# Qwiic_GPIO.net
KiCad netlist of a schematic drawn in EAGLE
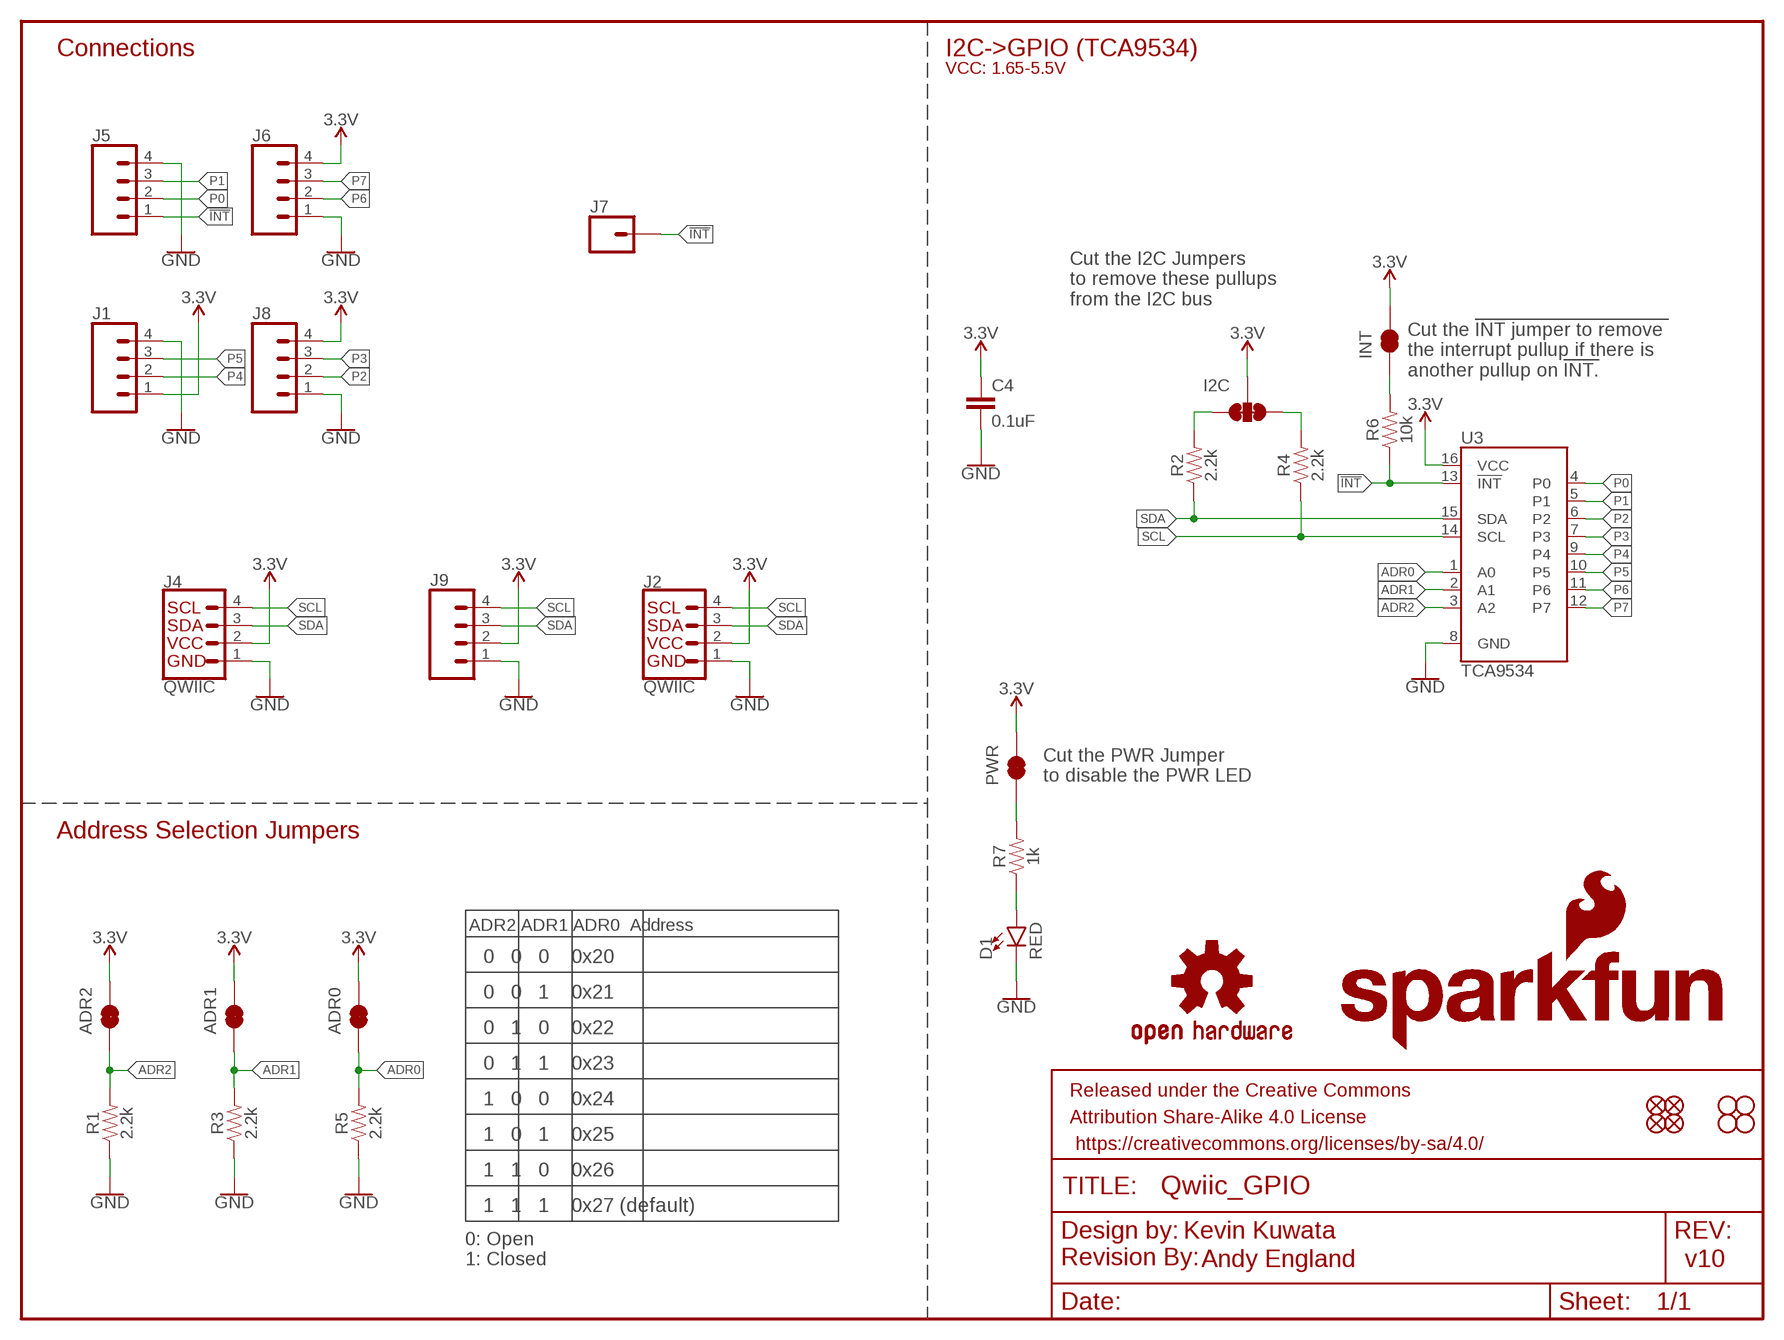
[diagram p0: schematic, sheet 1]

(export (version "E")
  (design (tool "Eeschema 10.0.6"))
  (components
    (comp (ref "ADR0")
      (value "JUMPER-SMT_2_NC_TRACE_SILK")
      (footprint "eagle-import:SMT-JUMPER_2_NC_TRACE_SILK")
      (libsource (lib "eagle-import") (part "JUMPER-SMT_2_NC_TRACE_SILK"))
    )
    (comp (ref "ADR1")
      (value "JUMPER-SMT_2_NC_TRACE_SILK")
      (footprint "eagle-import:SMT-JUMPER_2_NC_TRACE_SILK")
      (libsource (lib "eagle-import") (part "JUMPER-SMT_2_NC_TRACE_SILK"))
    )
    (comp (ref "ADR2")
      (value "JUMPER-SMT_2_NC_TRACE_SILK")
      (footprint "eagle-import:SMT-JUMPER_2_NC_TRACE_SILK")
      (libsource (lib "eagle-import") (part "JUMPER-SMT_2_NC_TRACE_SILK"))
    )
    (comp (ref "C4")
      (value "0.1uF")
      (footprint "eagle-import:0603")
      (libsource (lib "eagle-import") (part "0.1UF-0603-25V-(+80/-20%)"))
    )
    (comp (ref "D1")
      (value "RED")
      (footprint "eagle-import:LED-0603")
      (libsource (lib "eagle-import") (part "LED-RED0603"))
    )
    (comp (ref "FD1")
      (value "FIDUCIAL1X2")
      (footprint "eagle-import:FIDUCIAL-1X2")
      (libsource (lib "eagle-import") (part "SparkFun-Aesthetics_FIDUCIAL1X2"))
    )
    (comp (ref "FD2")
      (value "FIDUCIAL1X2")
      (footprint "eagle-import:FIDUCIAL-1X2")
      (libsource (lib "eagle-import") (part "SparkFun-Aesthetics_FIDUCIAL1X2"))
    )
    (comp (ref "FRAME1")
      (value "FRAME-LETTER")
      (footprint "eagle-import:CREATIVE_COMMONS")
      (libsource (lib "eagle-import") (part "FRAME-LETTER"))
    )
    (comp (ref "H1")
      (value "STAND-OFF")
      (footprint "eagle-import:STAND-OFF")
      (libsource (lib "eagle-import") (part "SparkFun-Hardware_STAND-OFF"))
    )
    (comp (ref "H2")
      (value "STAND-OFF")
      (footprint "eagle-import:STAND-OFF")
      (libsource (lib "eagle-import") (part "SparkFun-Hardware_STAND-OFF"))
    )
    (comp (ref "I2C")
      (value "JUMPER-SMT_3_2-NC_TRACE_SILK")
      (footprint "eagle-import:SMT-JUMPER_3_2-NC_TRACE_SILK")
      (libsource (lib "eagle-import") (part "JUMPER-SMT_3_2-NC_TRACE_SILK"))
    )
    (comp (ref "INT")
      (value "JUMPER-SMT_2_NC_TRACE_SILK")
      (footprint "eagle-import:SMT-JUMPER_2_NC_TRACE_SILK")
      (libsource (lib "eagle-import") (part "JUMPER-SMT_2_NC_TRACE_SILK"))
    )
    (comp (ref "J1")
      (value "CONN_04LATCH")
      (footprint "eagle-import:LATCHTERMINAL-5MM-4")
      (fields (field (name "PROD_ID") "CON-14722"))
      (libsource (lib "eagle-import") (part "CONN_04LATCH"))
    )
    (comp (ref "J2")
      (value "QWIIC")
      (footprint "eagle-import:JST04_1MM_RA")
      (fields (field (name "PROD_ID") "CONN-13694"))
      (libsource (lib "eagle-import") (part "QWIIC_CONNECTORJS-1MM"))
    )
    (comp (ref "J4")
      (value "QWIIC")
      (footprint "eagle-import:JST04_1MM_RA")
      (fields (field (name "PROD_ID") "CONN-13694"))
      (libsource (lib "eagle-import") (part "QWIIC_CONNECTORJS-1MM"))
    )
    (comp (ref "J5")
      (value "CONN_04LATCH")
      (footprint "eagle-import:LATCHTERMINAL-5MM-4")
      (fields (field (name "PROD_ID") "CON-14722"))
      (libsource (lib "eagle-import") (part "CONN_04LATCH"))
    )
    (comp (ref "J6")
      (value "CONN_04LATCH")
      (footprint "eagle-import:LATCHTERMINAL-5MM-4")
      (fields (field (name "PROD_ID") "CON-14722"))
      (libsource (lib "eagle-import") (part "CONN_04LATCH"))
    )
    (comp (ref "J7")
      (value "CONN_01PTH_NO_SILK_YES_STOP")
      (footprint "eagle-import:1X01_NO_SILK")
      (libsource (lib "eagle-import") (part "CONN_01PTH_NO_SILK_YES_STOP"))
    )
    (comp (ref "J8")
      (value "CONN_04LATCH")
      (footprint "eagle-import:LATCHTERMINAL-5MM-4")
      (fields (field (name "PROD_ID") "CON-14722"))
      (libsource (lib "eagle-import") (part "CONN_04LATCH"))
    )
    (comp (ref "J9")
      (value "CONN_041X04_NO_SILK")
      (footprint "eagle-import:1X04_NO_SILK")
      (libsource (lib "eagle-import") (part "CONN_041X04_NO_SILK"))
    )
    (comp (ref "JP2")
      (value "FIDUCIAL1X2")
      (footprint "eagle-import:FIDUCIAL-1X2")
      (libsource (lib "eagle-import") (part "FIDUCIAL1X2"))
    )
    (comp (ref "JP3")
      (value "STAND-OFF")
      (footprint "eagle-import:STAND-OFF")
      (libsource (lib "eagle-import") (part "STAND-OFF"))
    )
    (comp (ref "JP4")
      (value "STAND-OFF")
      (footprint "eagle-import:STAND-OFF")
      (libsource (lib "eagle-import") (part "STAND-OFF"))
    )
    (comp (ref "JP6")
      (value "FIDUCIAL1X2")
      (footprint "eagle-import:FIDUCIAL-1X2")
      (libsource (lib "eagle-import") (part "FIDUCIAL1X2"))
    )
    (comp (ref "LOGO1")
      (value "OSHW-LOGOMINI")
      (footprint "eagle-import:OSHW-LOGO-MINI")
      (libsource (lib "eagle-import") (part "OSHW-LOGOMINI"))
    )
    (comp (ref "LOGO2")
      (value "REVISION")
      (footprint "eagle-import:REVISION")
      (libsource (lib "eagle-import") (part "REVISION"))
    )
    (comp (ref "LOGO3")
      (value "SFE_LOGO_NAME_FLAME.1_INCH")
      (footprint "eagle-import:SFE_LOGO_NAME_FLAME_.1")
      (libsource (lib "eagle-import") (part "SFE_LOGO_NAME_FLAME.1_INCH"))
    )
    (comp (ref "LOGO4")
      (value "SFE_LOGO_FLAME.2_INCH")
      (footprint "eagle-import:SFE_LOGO_FLAME_.2")
      (libsource (lib "eagle-import") (part "SFE_LOGO_FLAME.2_INCH"))
    )
    (comp (ref "PWR")
      (value "JUMPER-SMT_2_NC_TRACE_SILK")
      (footprint "eagle-import:SMT-JUMPER_2_NC_TRACE_SILK")
      (libsource (lib "eagle-import") (part "JUMPER-SMT_2_NC_TRACE_SILK"))
    )
    (comp (ref "R1")
      (value "2.2k")
      (footprint "eagle-import:0603")
      (libsource (lib "eagle-import") (part "2.2KOHM-0603-1/10W-1%"))
    )
    (comp (ref "R2")
      (value "2.2k")
      (footprint "eagle-import:0603")
      (libsource (lib "eagle-import") (part "2.2KOHM-0603-1/10W-1%"))
    )
    (comp (ref "R3")
      (value "2.2k")
      (footprint "eagle-import:0603")
      (libsource (lib "eagle-import") (part "2.2KOHM-0603-1/10W-1%"))
    )
    (comp (ref "R4")
      (value "2.2k")
      (footprint "eagle-import:0603")
      (libsource (lib "eagle-import") (part "2.2KOHM-0603-1/10W-1%"))
    )
    (comp (ref "R5")
      (value "2.2k")
      (footprint "eagle-import:0603")
      (libsource (lib "eagle-import") (part "2.2KOHM-0603-1/10W-1%"))
    )
    (comp (ref "R6")
      (value "10k")
      (footprint "eagle-import:0603")
      (libsource (lib "eagle-import") (part "10KOHM-0603-1/10W-1%"))
    )
    (comp (ref "R7")
      (value "1k")
      (footprint "eagle-import:0603")
      (libsource (lib "eagle-import") (part "1KOHM-0603-1/10W-1%"))
    )
    (comp (ref "U3")
      (value "TCA9534")
      (footprint "eagle-import:16SOIC")
      (libsource (lib "eagle-import") (part "TCA9534U"))
    )
  )
  (nets
    (net (code "1") (name "/~{INT}") (class "Default")
      (node (ref "J5") (pin "1") (pinfunction "1_1") (pintype "passive"))
      (node (ref "J7") (pin "1") (pinfunction "1_1") (pintype "passive"))
      (node (ref "R6") (pin "1") (pinfunction "1_1") (pintype "passive"))
      (node (ref "U3") (pin "13") (pinfunction "~{INT}_13") (pintype "bidirectional"))
    )
    (net (code "2") (name "3.3V") (class "Default")
      (node (ref "ADR0") (pin "2") (pinfunction "2_2") (pintype "passive"))
      (node (ref "ADR1") (pin "2") (pinfunction "2_2") (pintype "passive"))
      (node (ref "ADR2") (pin "2") (pinfunction "2_2") (pintype "passive"))
      (node (ref "C4") (pin "1") (pinfunction "1_1") (pintype "passive"))
      (node (ref "I2C") (pin "2") (pinfunction "2_2") (pintype "passive"))
      (node (ref "INT") (pin "2") (pinfunction "2_2") (pintype "passive"))
      (node (ref "J1") (pin "1") (pinfunction "1_1") (pintype "passive"))
      (node (ref "J2") (pin "2") (pinfunction "2_2") (pintype "power_in"))
      (node (ref "J4") (pin "2") (pinfunction "2_2") (pintype "power_in"))
      (node (ref "J6") (pin "4") (pinfunction "4_4") (pintype "passive"))
      (node (ref "J8") (pin "4") (pinfunction "4_4") (pintype "passive"))
      (node (ref "J9") (pin "2") (pinfunction "2_2") (pintype "passive"))
      (node (ref "PWR") (pin "2") (pinfunction "2_2") (pintype "passive"))
      (node (ref "U3") (pin "16") (pinfunction "VCC_16") (pintype "bidirectional"))
    )
    (net (code "3") (name "ADR0") (class "Default")
      (node (ref "ADR0") (pin "1") (pinfunction "1_1") (pintype "passive"))
      (node (ref "R5") (pin "2") (pinfunction "2_2") (pintype "passive"))
      (node (ref "U3") (pin "1") (pinfunction "A0_1") (pintype "bidirectional"))
    )
    (net (code "4") (name "ADR1") (class "Default")
      (node (ref "ADR1") (pin "1") (pinfunction "1_1") (pintype "passive"))
      (node (ref "R3") (pin "2") (pinfunction "2_2") (pintype "passive"))
      (node (ref "U3") (pin "2") (pinfunction "A1_2") (pintype "bidirectional"))
    )
    (net (code "5") (name "ADR2") (class "Default")
      (node (ref "ADR2") (pin "1") (pinfunction "1_1") (pintype "passive"))
      (node (ref "R1") (pin "2") (pinfunction "2_2") (pintype "passive"))
      (node (ref "U3") (pin "3") (pinfunction "A2_3") (pintype "bidirectional"))
    )
    (net (code "6") (name "GND") (class "Default")
      (node (ref "C4") (pin "2") (pinfunction "2_2") (pintype "passive"))
      (node (ref "D1") (pin "C") (pinfunction "C_C") (pintype "passive"))
      (node (ref "J1") (pin "4") (pinfunction "4_4") (pintype "passive"))
      (node (ref "J2") (pin "1") (pinfunction "1_1") (pintype "power_in"))
      (node (ref "J4") (pin "1") (pinfunction "1_1") (pintype "power_in"))
      (node (ref "J5") (pin "4") (pinfunction "4_4") (pintype "passive"))
      (node (ref "J6") (pin "1") (pinfunction "1_1") (pintype "passive"))
      (node (ref "J8") (pin "1") (pinfunction "1_1") (pintype "passive"))
      (node (ref "J9") (pin "1") (pinfunction "1_1") (pintype "passive"))
      (node (ref "R1") (pin "1") (pinfunction "1_1") (pintype "passive"))
      (node (ref "R3") (pin "1") (pinfunction "1_1") (pintype "passive"))
      (node (ref "R5") (pin "1") (pinfunction "1_1") (pintype "passive"))
      (node (ref "U3") (pin "8") (pinfunction "GND_8") (pintype "bidirectional"))
    )
    (net (code "7") (name "Net-(D1-PadA)") (class "Default")
      (node (ref "D1") (pin "A") (pinfunction "A_A") (pintype "passive"))
      (node (ref "R7") (pin "1") (pinfunction "1_1") (pintype "passive"))
    )
    (net (code "8") (name "Net-(I2C-Pad1)") (class "Default")
      (node (ref "I2C") (pin "1") (pinfunction "1_1") (pintype "passive"))
      (node (ref "R2") (pin "2") (pinfunction "2_2") (pintype "passive"))
    )
    (net (code "9") (name "Net-(I2C-Pad3)") (class "Default")
      (node (ref "I2C") (pin "3") (pinfunction "3_3") (pintype "passive"))
      (node (ref "R4") (pin "2") (pinfunction "2_2") (pintype "passive"))
    )
    (net (code "10") (name "Net-(INT-Pad1)") (class "Default")
      (node (ref "INT") (pin "1") (pinfunction "1_1") (pintype "passive"))
      (node (ref "R6") (pin "2") (pinfunction "2_2") (pintype "passive"))
    )
    (net (code "11") (name "Net-(PWR-Pad1)") (class "Default")
      (node (ref "PWR") (pin "1") (pinfunction "1_1") (pintype "passive"))
      (node (ref "R7") (pin "2") (pinfunction "2_2") (pintype "passive"))
    )
    (net (code "12") (name "P0") (class "Default")
      (node (ref "J5") (pin "2") (pinfunction "2_2") (pintype "passive"))
      (node (ref "U3") (pin "4") (pinfunction "P0_4") (pintype "bidirectional"))
    )
    (net (code "13") (name "P1") (class "Default")
      (node (ref "J5") (pin "3") (pinfunction "3_3") (pintype "passive"))
      (node (ref "U3") (pin "5") (pinfunction "P1_5") (pintype "bidirectional"))
    )
    (net (code "14") (name "P2") (class "Default")
      (node (ref "J8") (pin "2") (pinfunction "2_2") (pintype "passive"))
      (node (ref "U3") (pin "6") (pinfunction "P2_6") (pintype "bidirectional"))
    )
    (net (code "15") (name "P3") (class "Default")
      (node (ref "J8") (pin "3") (pinfunction "3_3") (pintype "passive"))
      (node (ref "U3") (pin "7") (pinfunction "P3_7") (pintype "bidirectional"))
    )
    (net (code "16") (name "P4") (class "Default")
      (node (ref "J1") (pin "2") (pinfunction "2_2") (pintype "passive"))
      (node (ref "U3") (pin "9") (pinfunction "P4_9") (pintype "bidirectional"))
    )
    (net (code "17") (name "P5") (class "Default")
      (node (ref "J1") (pin "3") (pinfunction "3_3") (pintype "passive"))
      (node (ref "U3") (pin "10") (pinfunction "P5_10") (pintype "bidirectional"))
    )
    (net (code "18") (name "P6") (class "Default")
      (node (ref "J6") (pin "2") (pinfunction "2_2") (pintype "passive"))
      (node (ref "U3") (pin "11") (pinfunction "P6_11") (pintype "bidirectional"))
    )
    (net (code "19") (name "P7") (class "Default")
      (node (ref "J6") (pin "3") (pinfunction "3_3") (pintype "passive"))
      (node (ref "U3") (pin "12") (pinfunction "P7_12") (pintype "bidirectional"))
    )
    (net (code "20") (name "SCL") (class "Default")
      (node (ref "J2") (pin "4") (pinfunction "4_4") (pintype "passive"))
      (node (ref "J4") (pin "4") (pinfunction "4_4") (pintype "passive"))
      (node (ref "J9") (pin "4") (pinfunction "4_4") (pintype "passive"))
      (node (ref "R4") (pin "1") (pinfunction "1_1") (pintype "passive"))
      (node (ref "U3") (pin "14") (pinfunction "SCL_14") (pintype "bidirectional"))
    )
    (net (code "21") (name "SDA") (class "Default")
      (node (ref "J2") (pin "3") (pinfunction "3_3") (pintype "passive"))
      (node (ref "J4") (pin "3") (pinfunction "3_3") (pintype "passive"))
      (node (ref "J9") (pin "3") (pinfunction "3_3") (pintype "passive"))
      (node (ref "R2") (pin "1") (pinfunction "1_1") (pintype "passive"))
      (node (ref "U3") (pin "15") (pinfunction "SDA_15") (pintype "bidirectional"))
    )
  )
)
